# Orisec_Connect_Ethernet.net
KiCad netlist of a schematic drawn in EasyEDA Pro
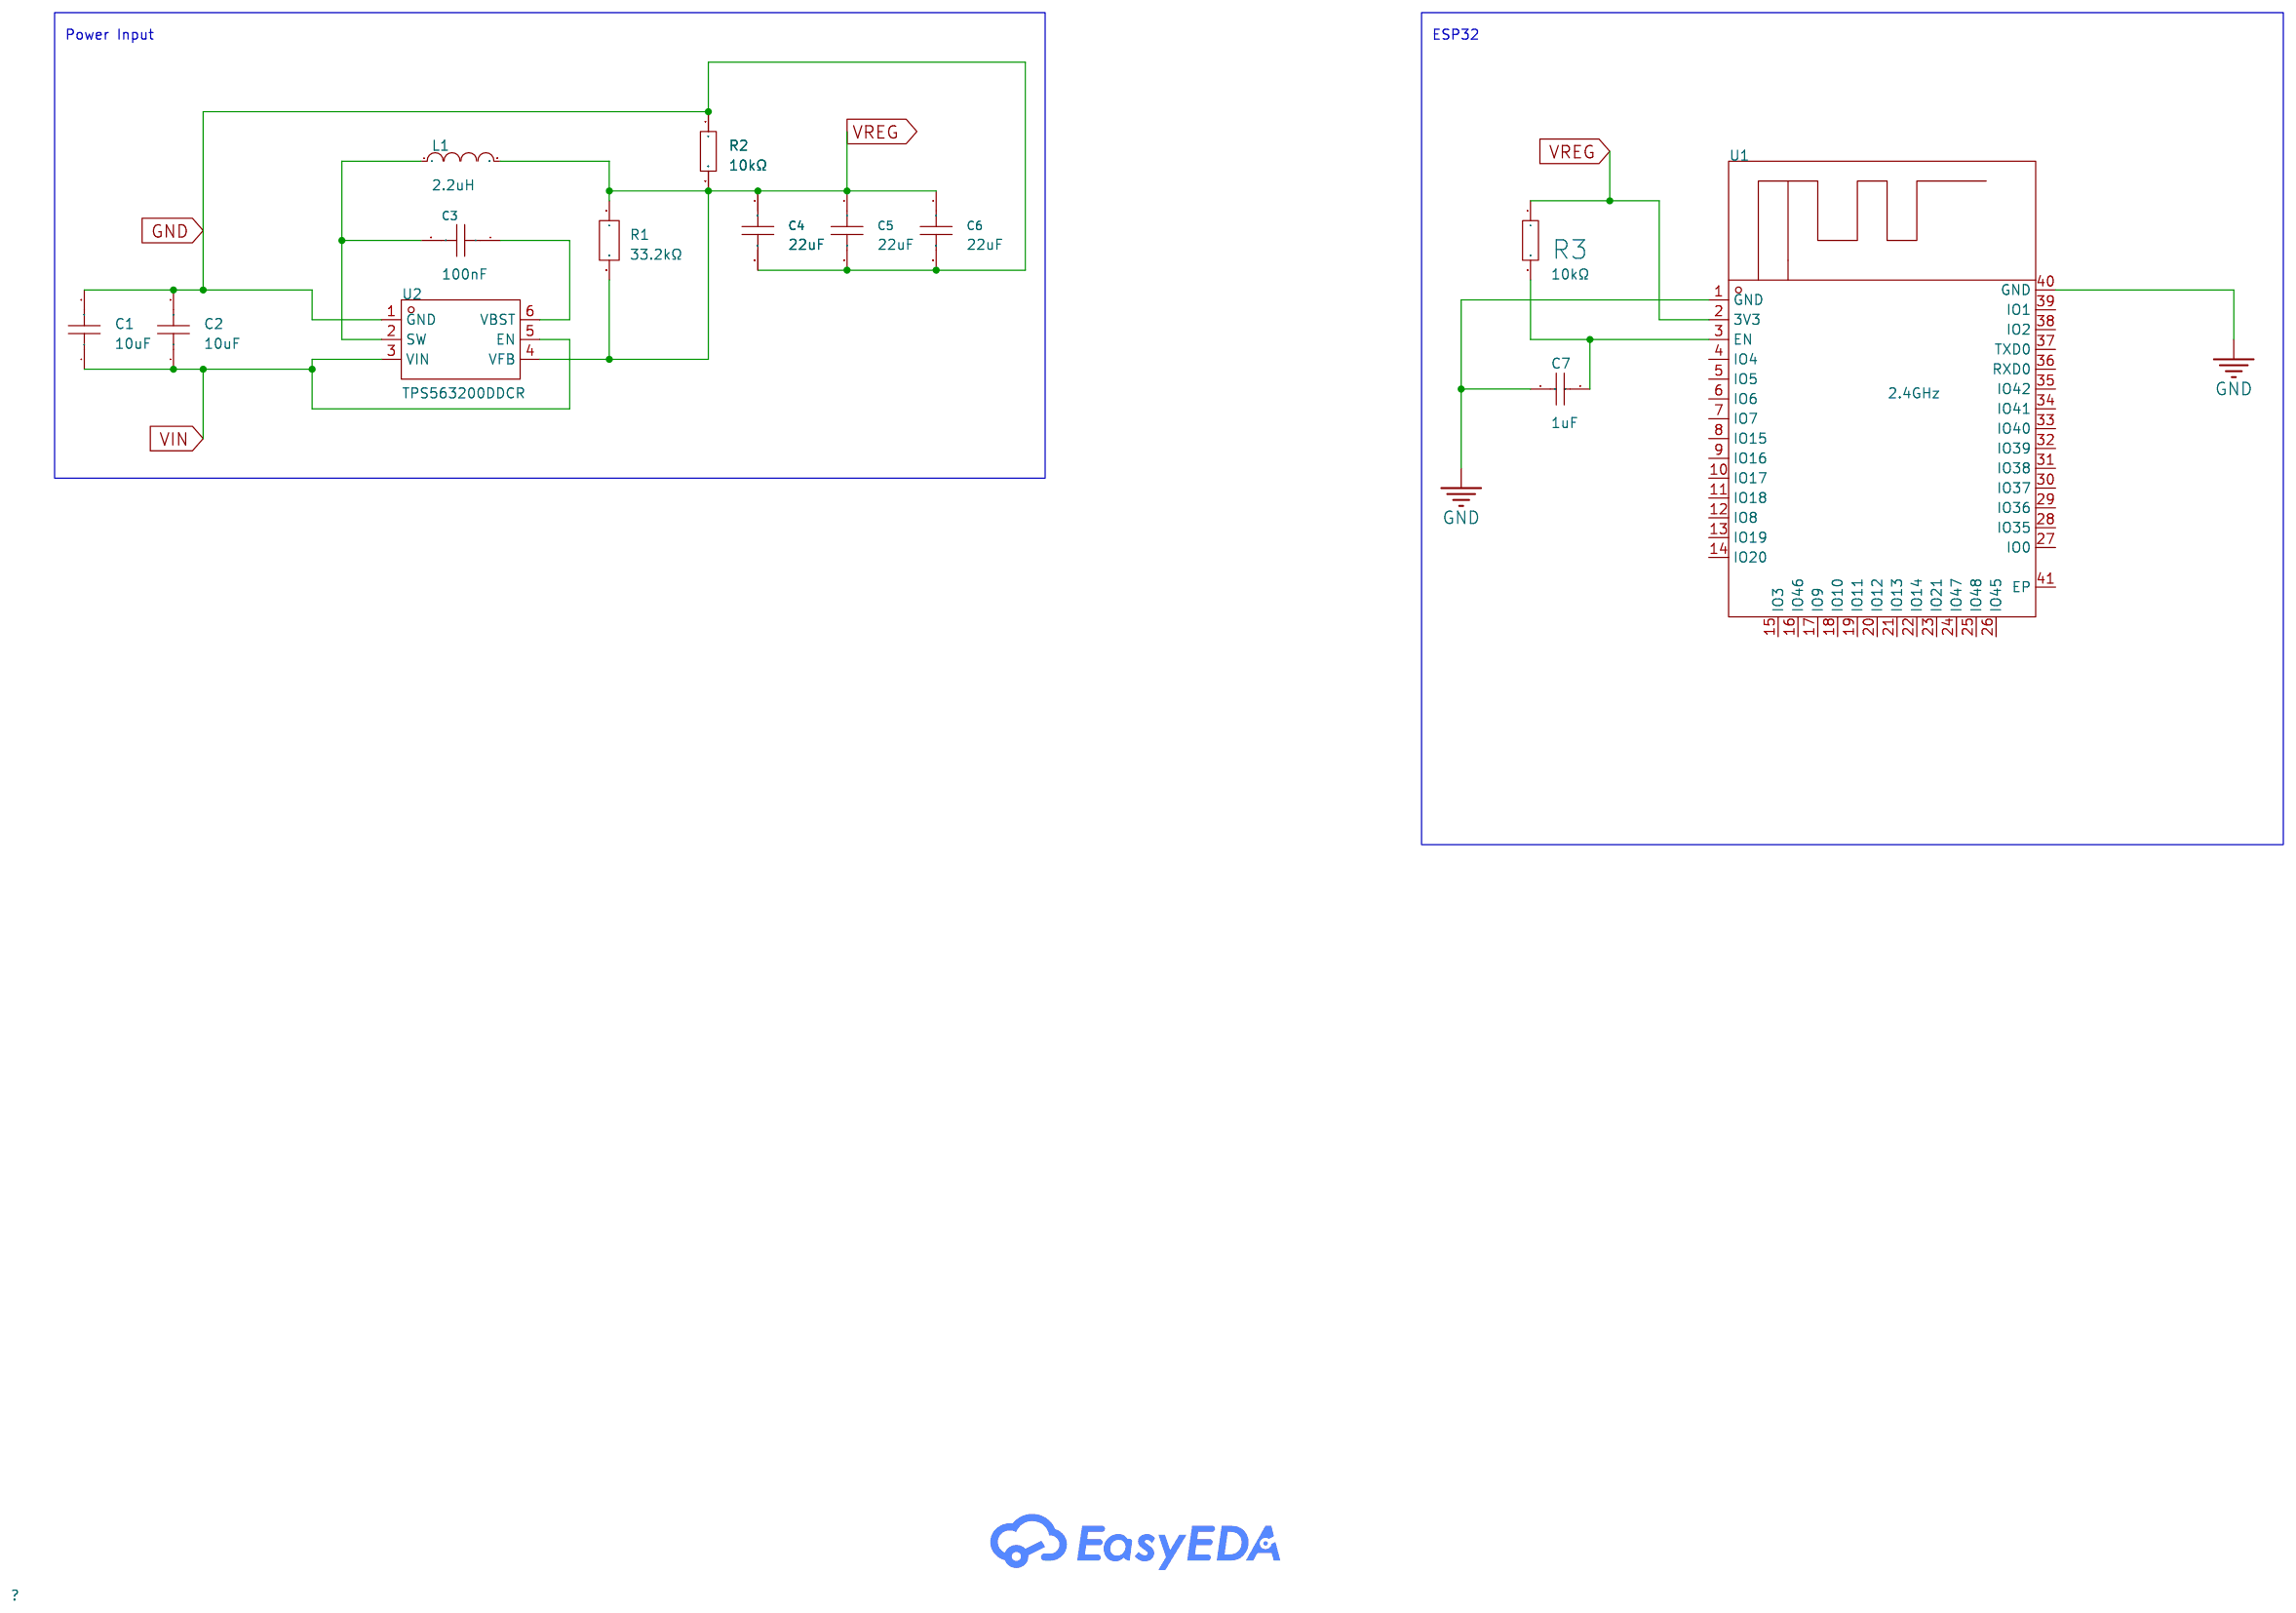
[diagram p0: schematic sheet]

(export (version "E")
  (design (tool "Eeschema 10.0.6"))
  (components
    (comp (ref "C1")
      (value "10uF")
      (footprint "easyedapro:C0805")
      (description "Capacitance:10uF Tolerance:±10% Tolerance:±10% Voltage Rating:25V Temperature Coefficient:X5R")
      (fields
        (field (name "Manufacturer Part") "MSAST219LB5106KTNA01")
        (field (name "Manufacturer") "TAIYO YUDEN(太诱)")
      )
      (libsource (lib "easyedapro") (part "MSAST219LB5106KTNA01"))
    )
    (comp (ref "C2")
      (value "10uF")
      (footprint "easyedapro:C0805")
      (description "Capacitance:10uF Tolerance:±10% Tolerance:±10% Voltage Rating:25V Temperature Coefficient:X5R")
      (fields
        (field (name "Manufacturer Part") "MSAST219LB5106KTNA01")
        (field (name "Manufacturer") "TAIYO YUDEN(太诱)")
      )
      (libsource (lib "easyedapro") (part "MSAST219LB5106KTNA01"))
    )
    (comp (ref "C3")
      (value "100nF")
      (footprint "easyedapro:C0805")
      (fields (field (name "Manufacturer Part") "08053C104KAT2A") (field (name "Manufacturer") "Kyocera AVX"))
      (libsource (lib "easyedapro") (part "08053C104KAT2A"))
    )
    (comp (ref "C4")
      (value "22uF")
      (footprint "easyedapro:C0603")
      (description "Capacitance:22uF Tolerance:±20% Tolerance:±20% Voltage Rating:6.3V Temperature Coefficient:X5R")
      (fields
        (field (name "Manufacturer Part") "GRM188R60J226MEA0D")
        (field (name "Manufacturer") "muRata(村田)")
      )
      (libsource (lib "easyedapro") (part "GRM188R60J226MEA0D"))
    )
    (comp (ref "C5")
      (value "22uF")
      (footprint "easyedapro:C0603")
      (description "Capacitance:22uF Tolerance:±20% Tolerance:±20% Voltage Rating:6.3V Temperature Coefficient:X5R")
      (fields
        (field (name "Manufacturer Part") "GRM188R60J226MEA0D")
        (field (name "Manufacturer") "muRata(村田)")
      )
      (libsource (lib "easyedapro") (part "GRM188R60J226MEA0D"))
    )
    (comp (ref "C6")
      (value "22uF")
      (footprint "easyedapro:C0603")
      (description "Capacitance:22uF Tolerance:±20% Tolerance:±20% Voltage Rating:6.3V Temperature Coefficient:X5R")
      (fields
        (field (name "Manufacturer Part") "GRM188R60J226MEA0D")
        (field (name "Manufacturer") "muRata(村田)")
      )
      (libsource (lib "easyedapro") (part "GRM188R60J226MEA0D"))
    )
    (comp (ref "C7")
      (value "1uF")
      (footprint "easyedapro:C0402")
      (description "Capacitance:1uF Tolerance:±10% Tolerance:±10% Voltage Rating:10V Temperature Coefficient:X5R")
      (fields
        (field (name "Manufacturer Part") "CL05A105KP5NNNC")
        (field (name "Manufacturer") "SAMSUNG(三星)")
      )
      (libsource (lib "easyedapro") (part "CL05A105KP5NNNC"))
    )
    (comp (ref "L1")
      (value "2.2uH")
      (footprint "easyedapro:IND-SMD_L7.0-W6.6")
      (fields
        (field (name "Manufacturer Part") "CY0630AT125DS-2R2MC")
        (field (name "Manufacturer") "Sumida(胜美达)")
      )
      (libsource (lib "easyedapro") (part "CY0630AT125DS-2R2MC"))
    )
    (comp (ref "R1")
      (value "33.2kΩ")
      (footprint "easyedapro:R0402")
      (fields
        (field (name "Manufacturer Part") "CRCW040233K2FKED")
        (field (name "Manufacturer") "VISHAY(威世)")
      )
      (libsource (lib "easyedapro") (part "CRCW040233K2FKED"))
    )
    (comp (ref "R2")
      (value "10kΩ")
      (footprint "easyedapro:R0201")
      (fields (field (name "Manufacturer Part") "RC0201FR-0710KL") (field (name "Manufacturer") "YAGEO(国巨)"))
      (libsource (lib "easyedapro") (part "RC0201FR-0710KL"))
    )
    (comp (ref "R3")
      (value "10kΩ")
      (footprint "easyedapro:R0603")
      (fields
        (field (name "Manufacturer Part") "0603WAF1002T5E")
        (field (name "Manufacturer") "UNI-ROYAL(厚声)")
      )
      (libsource (lib "easyedapro") (part "0603WAF1002T5E"))
    )
    (comp (ref "U1")
      (value "2.4GHz")
      (footprint "easyedapro:WIFIM-SMD_ESP32-S3-WROOM-1-N8")
      (description "Core Processor:ESP32-S3 Chip Support Interface:I2C；GPIO；SPI；PWM；ADC；UART；USB；I2S Frequency:2.4GHz")
      (fields
        (field (name "Manufacturer Part") "ESP32-S3-WROOM-1-N8")
        (field (name "Manufacturer") "ESPRESSIF(乐鑫)")
      )
      (libsource (lib "easyedapro") (part "ESP32-S3-WROOM-1-N8"))
    )
    (comp (ref "U2")
      (value "TPS563200DDCR")
      (footprint "easyedapro:SOT-23-6_L2.9-W1.6-P0.95-LS2.8-BR")
      (fields (field (name "Manufacturer") "TI(德州仪器)"))
      (libsource (lib "easyedapro") (part "TPS563200DDCR"))
    )
  )
  (nets
    (net (code "1") (name "GND") (class "Default")
      (node (ref "C1") (pin "2") (pinfunction "2_2") (pintype "unspecified"))
      (node (ref "C2") (pin "2") (pinfunction "2_2") (pintype "unspecified"))
      (node (ref "C4") (pin "2") (pinfunction "2_2") (pintype "input"))
      (node (ref "C5") (pin "2") (pinfunction "2_2") (pintype "input"))
      (node (ref "C6") (pin "2") (pinfunction "2_2") (pintype "input"))
      (node (ref "C7") (pin "1") (pinfunction "1_1") (pintype "input"))
      (node (ref "R2") (pin "1") (pinfunction "1_1") (pintype "input"))
      (node (ref "U1") (pin "1") (pinfunction "GND_1") (pintype "unspecified"))
      (node (ref "U1") (pin "40") (pinfunction "GND_40") (pintype "unspecified"))
      (node (ref "U2") (pin "1") (pinfunction "GND_1") (pintype "unspecified"))
    )
    (net (code "2") (name "Net-(U1-EN)") (class "Default")
      (node (ref "C7") (pin "2") (pinfunction "2_2") (pintype "input"))
      (node (ref "R3") (pin "2") (pinfunction "2_2") (pintype "input"))
      (node (ref "U1") (pin "3") (pinfunction "EN_3") (pintype "unspecified"))
    )
    (net (code "3") (name "Net-(U2-SW)") (class "Default")
      (node (ref "C3") (pin "2") (pinfunction "2_2") (pintype "input"))
      (node (ref "L1") (pin "1") (pinfunction "1_1") (pintype "unspecified"))
      (node (ref "U2") (pin "2") (pinfunction "SW_2") (pintype "unspecified"))
    )
    (net (code "4") (name "Net-(U2-VBST)") (class "Default")
      (node (ref "C3") (pin "1") (pinfunction "1_1") (pintype "input"))
      (node (ref "U2") (pin "6") (pinfunction "VBST_6") (pintype "unspecified"))
    )
    (net (code "5") (name "VIN") (class "Default")
      (node (ref "C1") (pin "1") (pinfunction "1_1") (pintype "unspecified"))
      (node (ref "C2") (pin "1") (pinfunction "1_1") (pintype "unspecified"))
      (node (ref "U2") (pin "3") (pinfunction "VIN_3") (pintype "unspecified"))
      (node (ref "U2") (pin "5") (pinfunction "EN_5") (pintype "unspecified"))
    )
    (net (code "6") (name "VREG") (class "Default")
      (node (ref "C4") (pin "1") (pinfunction "1_1") (pintype "input"))
      (node (ref "C5") (pin "1") (pinfunction "1_1") (pintype "input"))
      (node (ref "C6") (pin "1") (pinfunction "1_1") (pintype "input"))
      (node (ref "L1") (pin "2") (pinfunction "2_2") (pintype "unspecified"))
      (node (ref "R1") (pin "1") (pinfunction "1_1") (pintype "unspecified"))
      (node (ref "R1") (pin "2") (pinfunction "2_2") (pintype "unspecified"))
      (node (ref "R2") (pin "2") (pinfunction "2_2") (pintype "input"))
      (node (ref "R3") (pin "1") (pinfunction "1_1") (pintype "input"))
      (node (ref "U1") (pin "2") (pinfunction "3V3_2") (pintype "unspecified"))
      (node (ref "U2") (pin "4") (pinfunction "VFB_4") (pintype "unspecified"))
    )
    (net (code "7") (name "unconnected-(U1-EP-Pad41)") (class "Default")
      (node (ref "U1") (pin "41") (pinfunction "EP_41") (pintype "unspecified"))
    )
    (net (code "8") (name "unconnected-(U1-IO0-Pad27)") (class "Default")
      (node (ref "U1") (pin "27") (pinfunction "IO0_27") (pintype "unspecified"))
    )
    (net (code "9") (name "unconnected-(U1-IO1-Pad39)") (class "Default")
      (node (ref "U1") (pin "39") (pinfunction "IO1_39") (pintype "unspecified"))
    )
    (net (code "10") (name "unconnected-(U1-IO2-Pad38)") (class "Default")
      (node (ref "U1") (pin "38") (pinfunction "IO2_38") (pintype "unspecified"))
    )
    (net (code "11") (name "unconnected-(U1-IO3-Pad15)") (class "Default")
      (node (ref "U1") (pin "15") (pinfunction "IO3_15") (pintype "unspecified"))
    )
    (net (code "12") (name "unconnected-(U1-IO4-Pad4)") (class "Default")
      (node (ref "U1") (pin "4") (pinfunction "IO4_4") (pintype "unspecified"))
    )
    (net (code "13") (name "unconnected-(U1-IO5-Pad5)") (class "Default")
      (node (ref "U1") (pin "5") (pinfunction "IO5_5") (pintype "unspecified"))
    )
    (net (code "14") (name "unconnected-(U1-IO6-Pad6)") (class "Default")
      (node (ref "U1") (pin "6") (pinfunction "IO6_6") (pintype "unspecified"))
    )
    (net (code "15") (name "unconnected-(U1-IO7-Pad7)") (class "Default")
      (node (ref "U1") (pin "7") (pinfunction "IO7_7") (pintype "unspecified"))
    )
    (net (code "16") (name "unconnected-(U1-IO8-Pad12)") (class "Default")
      (node (ref "U1") (pin "12") (pinfunction "IO8_12") (pintype "unspecified"))
    )
    (net (code "17") (name "unconnected-(U1-IO9-Pad17)") (class "Default")
      (node (ref "U1") (pin "17") (pinfunction "IO9_17") (pintype "unspecified"))
    )
    (net (code "18") (name "unconnected-(U1-IO10-Pad18)") (class "Default")
      (node (ref "U1") (pin "18") (pinfunction "IO10_18") (pintype "unspecified"))
    )
    (net (code "19") (name "unconnected-(U1-IO11-Pad19)") (class "Default")
      (node (ref "U1") (pin "19") (pinfunction "IO11_19") (pintype "unspecified"))
    )
    (net (code "20") (name "unconnected-(U1-IO12-Pad20)") (class "Default")
      (node (ref "U1") (pin "20") (pinfunction "IO12_20") (pintype "unspecified"))
    )
    (net (code "21") (name "unconnected-(U1-IO13-Pad21)") (class "Default")
      (node (ref "U1") (pin "21") (pinfunction "IO13_21") (pintype "unspecified"))
    )
    (net (code "22") (name "unconnected-(U1-IO14-Pad22)") (class "Default")
      (node (ref "U1") (pin "22") (pinfunction "IO14_22") (pintype "unspecified"))
    )
    (net (code "23") (name "unconnected-(U1-IO15-Pad8)") (class "Default")
      (node (ref "U1") (pin "8") (pinfunction "IO15_8") (pintype "unspecified"))
    )
    (net (code "24") (name "unconnected-(U1-IO16-Pad9)") (class "Default")
      (node (ref "U1") (pin "9") (pinfunction "IO16_9") (pintype "unspecified"))
    )
    (net (code "25") (name "unconnected-(U1-IO17-Pad10)") (class "Default")
      (node (ref "U1") (pin "10") (pinfunction "IO17_10") (pintype "unspecified"))
    )
    (net (code "26") (name "unconnected-(U1-IO18-Pad11)") (class "Default")
      (node (ref "U1") (pin "11") (pinfunction "IO18_11") (pintype "unspecified"))
    )
    (net (code "27") (name "unconnected-(U1-IO19-Pad13)") (class "Default")
      (node (ref "U1") (pin "13") (pinfunction "IO19_13") (pintype "unspecified"))
    )
    (net (code "28") (name "unconnected-(U1-IO20-Pad14)") (class "Default")
      (node (ref "U1") (pin "14") (pinfunction "IO20_14") (pintype "unspecified"))
    )
    (net (code "29") (name "unconnected-(U1-IO21-Pad23)") (class "Default")
      (node (ref "U1") (pin "23") (pinfunction "IO21_23") (pintype "unspecified"))
    )
    (net (code "30") (name "unconnected-(U1-IO35-Pad28)") (class "Default")
      (node (ref "U1") (pin "28") (pinfunction "IO35_28") (pintype "unspecified"))
    )
    (net (code "31") (name "unconnected-(U1-IO36-Pad29)") (class "Default")
      (node (ref "U1") (pin "29") (pinfunction "IO36_29") (pintype "unspecified"))
    )
    (net (code "32") (name "unconnected-(U1-IO37-Pad30)") (class "Default")
      (node (ref "U1") (pin "30") (pinfunction "IO37_30") (pintype "unspecified"))
    )
    (net (code "33") (name "unconnected-(U1-IO38-Pad31)") (class "Default")
      (node (ref "U1") (pin "31") (pinfunction "IO38_31") (pintype "unspecified"))
    )
    (net (code "34") (name "unconnected-(U1-IO39-Pad32)") (class "Default")
      (node (ref "U1") (pin "32") (pinfunction "IO39_32") (pintype "unspecified"))
    )
    (net (code "35") (name "unconnected-(U1-IO40-Pad33)") (class "Default")
      (node (ref "U1") (pin "33") (pinfunction "IO40_33") (pintype "unspecified"))
    )
    (net (code "36") (name "unconnected-(U1-IO41-Pad34)") (class "Default")
      (node (ref "U1") (pin "34") (pinfunction "IO41_34") (pintype "unspecified"))
    )
    (net (code "37") (name "unconnected-(U1-IO42-Pad35)") (class "Default")
      (node (ref "U1") (pin "35") (pinfunction "IO42_35") (pintype "unspecified"))
    )
    (net (code "38") (name "unconnected-(U1-IO45-Pad26)") (class "Default")
      (node (ref "U1") (pin "26") (pinfunction "IO45_26") (pintype "unspecified"))
    )
    (net (code "39") (name "unconnected-(U1-IO46-Pad16)") (class "Default")
      (node (ref "U1") (pin "16") (pinfunction "IO46_16") (pintype "unspecified"))
    )
    (net (code "40") (name "unconnected-(U1-IO47-Pad24)") (class "Default")
      (node (ref "U1") (pin "24") (pinfunction "IO47_24") (pintype "unspecified"))
    )
    (net (code "41") (name "unconnected-(U1-IO48-Pad25)") (class "Default")
      (node (ref "U1") (pin "25") (pinfunction "IO48_25") (pintype "unspecified"))
    )
    (net (code "42") (name "unconnected-(U1-RXD0-Pad36)") (class "Default")
      (node (ref "U1") (pin "36") (pinfunction "RXD0_36") (pintype "unspecified"))
    )
    (net (code "43") (name "unconnected-(U1-TXD0-Pad37)") (class "Default")
      (node (ref "U1") (pin "37") (pinfunction "TXD0_37") (pintype "unspecified"))
    )
  )
)
